# LMP848x_Breakout_v0_1.net
KiCad netlist of a schematic drawn in EAGLE
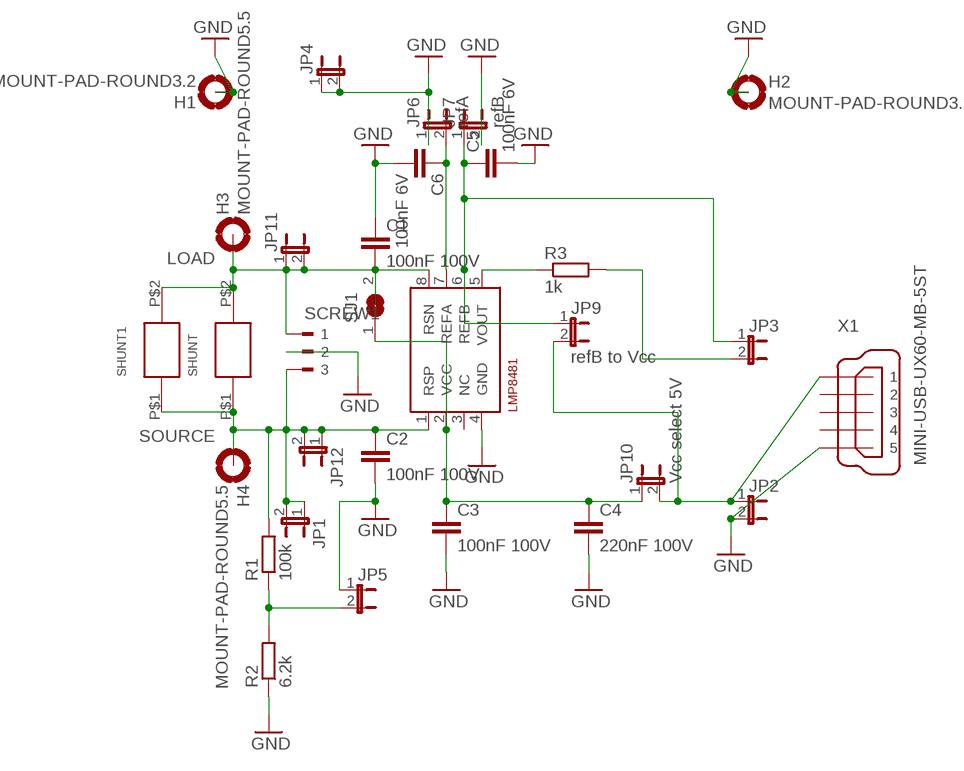
[diagram p0: schematic, sheet 1]

(export (version "E")
  (design (tool "Eeschema 10.0.6"))
  (components
    (comp (ref "C1")
      (value "100nF 100V")
      (footprint "eagle-import:C0805")
      (libsource (lib "eagle-import") (part "C-EUC0805"))
    )
    (comp (ref "C2")
      (value "100nF 100V")
      (footprint "eagle-import:C0805")
      (libsource (lib "eagle-import") (part "C-EUC0805"))
    )
    (comp (ref "C3")
      (value "100nF 100V")
      (footprint "eagle-import:C0805")
      (libsource (lib "eagle-import") (part "C-EUC0805"))
    )
    (comp (ref "C4")
      (value "220nF 100V")
      (footprint "eagle-import:C0805")
      (libsource (lib "eagle-import") (part "C-EUC0805"))
    )
    (comp (ref "C5")
      (value "100nF 6V")
      (footprint "eagle-import:C0805")
      (libsource (lib "eagle-import") (part "C-EUC0805"))
    )
    (comp (ref "C6")
      (value "100nF 6V")
      (footprint "eagle-import:C0805")
      (libsource (lib "eagle-import") (part "C-EUC0805"))
    )
    (comp (ref "H1")
      (value "MOUNT-PAD-ROUND3.2")
      (footprint "eagle-import:3,2-PAD")
      (libsource (lib "eagle-import") (part "MOUNT-PAD-ROUND3.2"))
    )
    (comp (ref "H2")
      (value "MOUNT-PAD-ROUND3.2")
      (footprint "eagle-import:3,2-PAD")
      (libsource (lib "eagle-import") (part "MOUNT-PAD-ROUND3.2"))
    )
    (comp (ref "H3")
      (value "MOUNT-PAD-ROUND5.5")
      (footprint "eagle-import:5,5-PAD")
      (libsource (lib "eagle-import") (part "MOUNT-PAD-ROUND5.5"))
    )
    (comp (ref "H4")
      (value "MOUNT-PAD-ROUND5.5")
      (footprint "eagle-import:5,5-PAD")
      (libsource (lib "eagle-import") (part "MOUNT-PAD-ROUND5.5"))
    )
    (comp (ref "JP1")
      (value "JP1E")
      (footprint "eagle-import:JP1")
      (libsource (lib "eagle-import") (part "JP1E"))
    )
    (comp (ref "JP2")
      (value "JP1E")
      (footprint "eagle-import:JP1")
      (libsource (lib "eagle-import") (part "JP1E"))
    )
    (comp (ref "JP3")
      (value "JP1E")
      (footprint "eagle-import:JP1")
      (libsource (lib "eagle-import") (part "JP1E"))
    )
    (comp (ref "JP4")
      (value "JP1E")
      (footprint "eagle-import:JP1")
      (libsource (lib "eagle-import") (part "JP1E"))
    )
    (comp (ref "JP5")
      (value "JP1E")
      (footprint "eagle-import:JP1")
      (libsource (lib "eagle-import") (part "JP1E"))
    )
    (comp (ref "JP6")
      (value "refA")
      (footprint "eagle-import:JP1")
      (libsource (lib "eagle-import") (part "JP1E"))
    )
    (comp (ref "JP7")
      (value "refB")
      (footprint "eagle-import:JP1")
      (libsource (lib "eagle-import") (part "JP1E"))
    )
    (comp (ref "JP9")
      (value "refB to Vcc")
      (footprint "eagle-import:JP1")
      (libsource (lib "eagle-import") (part "JP1E"))
    )
    (comp (ref "JP10")
      (value "Vcc select 5V")
      (footprint "eagle-import:JP1")
      (libsource (lib "eagle-import") (part "JP1E"))
    )
    (comp (ref "JP11")
      (value "JP1E")
      (footprint "eagle-import:JP1")
      (libsource (lib "eagle-import") (part "JP1E"))
    )
    (comp (ref "JP12")
      (value "JP1E")
      (footprint "eagle-import:JP1")
      (libsource (lib "eagle-import") (part "JP1E"))
    )
    (comp (ref "LMP8481")
      (value "LMP8481-H")
      (footprint "eagle-import:S-PDSO-G08")
      (libsource (lib "eagle-import") (part "LMP8481-H"))
    )
    (comp (ref "R1")
      (value "100k")
      (footprint "eagle-import:0207_7")
      (libsource (lib "eagle-import") (part "R-EU_0207/7"))
    )
    (comp (ref "R2")
      (value "6.2k")
      (footprint "eagle-import:0207_7")
      (libsource (lib "eagle-import") (part "R-EU_0207/7"))
    )
    (comp (ref "R3")
      (value "1k")
      (footprint "eagle-import:0204_5")
      (libsource (lib "eagle-import") (part "R-EU_0204/5"))
    )
    (comp (ref "SCREW1")
      (value "180-3")
      (footprint "eagle-import:180-3")
      (libsource (lib "eagle-import") (part "180-3"))
    )
    (comp (ref "SHUNT")
      (value "EBW_SERIES_15.2MM")
      (footprint "eagle-import:EBW_SERIES_15.2MM")
      (libsource (lib "eagle-import") (part "EBW_SERIES_15.2MM"))
    )
    (comp (ref "SHUNT1")
      (value "EBW_SERIES_15.2MM")
      (footprint "eagle-import:EBW_SERIES_15.2MM")
      (libsource (lib "eagle-import") (part "EBW_SERIES_15.2MM"))
    )
    (comp (ref "SJ1") (value "SJ") (footprint "eagle-import:SJ") (libsource (lib "eagle-import") (part "SJ")))
    (comp (ref "X1")
      (value "MINI-USB-UX60-MB-5ST")
      (footprint "eagle-import:UX60-MB-5ST")
      (libsource (lib "eagle-import") (part "MINI-USB-UX60-MB-5ST"))
    )
  )
  (nets
    (net (code "1") (name "/LOAD") (class "Default")
      (node (ref "C1") (pin "2") (pinfunction "2_2") (pintype "passive"))
      (node (ref "H3") (pin "B5,5") (pinfunction "MOUNT_B5,5") (pintype "passive"))
      (node (ref "JP11") (pin "1") (pinfunction "1_1") (pintype "passive"))
      (node (ref "JP11") (pin "2") (pinfunction "2_2") (pintype "passive"))
      (node (ref "LMP8481") (pin "8") (pinfunction "RSN_8") (pintype "bidirectional"))
      (node (ref "SCREW1") (pin "1") (pinfunction "1_1") (pintype "passive"))
      (node (ref "SHUNT") (pin "P$2") (pinfunction "P$2_P$2") (pintype "bidirectional"))
      (node (ref "SHUNT1") (pin "P$2") (pinfunction "P$2_P$2") (pintype "bidirectional"))
      (node (ref "SJ1") (pin "2") (pinfunction "2_2") (pintype "passive"))
    )
    (net (code "2") (name "/SOURCE") (class "Default")
      (node (ref "C2") (pin "1") (pinfunction "1_1") (pintype "passive"))
      (node (ref "H4") (pin "B5,5") (pinfunction "MOUNT_B5,5") (pintype "passive"))
      (node (ref "JP1") (pin "1") (pinfunction "1_1") (pintype "passive"))
      (node (ref "JP1") (pin "2") (pinfunction "2_2") (pintype "passive"))
      (node (ref "JP12") (pin "1") (pinfunction "1_1") (pintype "passive"))
      (node (ref "JP12") (pin "2") (pinfunction "2_2") (pintype "passive"))
      (node (ref "LMP8481") (pin "1") (pinfunction "RSP_1") (pintype "bidirectional"))
      (node (ref "R1") (pin "2") (pinfunction "2_2") (pintype "passive"))
      (node (ref "SCREW1") (pin "3") (pinfunction "3_3") (pintype "passive"))
      (node (ref "SHUNT") (pin "P$1") (pinfunction "P$1_P$1") (pintype "bidirectional"))
      (node (ref "SHUNT1") (pin "P$1") (pinfunction "P$1_P$1") (pintype "bidirectional"))
    )
    (net (code "3") (name "GND") (class "Default")
      (node (ref "C1") (pin "1") (pinfunction "1_1") (pintype "passive"))
      (node (ref "C2") (pin "2") (pinfunction "2_2") (pintype "passive"))
      (node (ref "C3") (pin "2") (pinfunction "2_2") (pintype "passive"))
      (node (ref "C4") (pin "2") (pinfunction "2_2") (pintype "passive"))
      (node (ref "C5") (pin "2") (pinfunction "2_2") (pintype "passive"))
      (node (ref "C6") (pin "2") (pinfunction "2_2") (pintype "passive"))
      (node (ref "H1") (pin "B3,2") (pinfunction "MOUNT_B3,2") (pintype "passive"))
      (node (ref "H2") (pin "B3,2") (pinfunction "MOUNT_B3,2") (pintype "passive"))
      (node (ref "JP2") (pin "2") (pinfunction "2_2") (pintype "passive"))
      (node (ref "JP4") (pin "1") (pinfunction "1_1") (pintype "passive"))
      (node (ref "JP4") (pin "2") (pinfunction "2_2") (pintype "passive"))
      (node (ref "JP5") (pin "1") (pinfunction "1_1") (pintype "passive"))
      (node (ref "JP6") (pin "1") (pinfunction "1_1") (pintype "passive"))
      (node (ref "JP7") (pin "2") (pinfunction "2_2") (pintype "passive"))
      (node (ref "LMP8481") (pin "4") (pinfunction "GND_4") (pintype "bidirectional"))
      (node (ref "R2") (pin "1") (pinfunction "1_1") (pintype "passive"))
      (node (ref "SCREW1") (pin "2") (pinfunction "2_2") (pintype "passive"))
      (node (ref "X1") (pin "5") (pinfunction "5_5") (pintype "input"))
    )
    (net (code "4") (name "Net-(JP3-Pad2)") (class "Default")
      (node (ref "JP3") (pin "2") (pinfunction "2_2") (pintype "passive"))
      (node (ref "R3") (pin "2") (pinfunction "2_2") (pintype "passive"))
    )
    (net (code "5") (name "Net-(JP5-Pad2)") (class "Default")
      (node (ref "JP5") (pin "2") (pinfunction "2_2") (pintype "passive"))
      (node (ref "R1") (pin "1") (pinfunction "1_1") (pintype "passive"))
      (node (ref "R2") (pin "2") (pinfunction "2_2") (pintype "passive"))
    )
    (net (code "6") (name "Net-(JP10-Pad2)") (class "Default")
      (node (ref "JP10") (pin "2") (pinfunction "2_2") (pintype "passive"))
      (node (ref "JP2") (pin "1") (pinfunction "1_1") (pintype "passive"))
      (node (ref "JP9") (pin "2") (pinfunction "2_2") (pintype "passive"))
      (node (ref "X1") (pin "1") (pinfunction "1_1") (pintype "input"))
    )
    (net (code "7") (name "Net-(LMP8481-REFA)") (class "Default")
      (node (ref "C6") (pin "1") (pinfunction "1_1") (pintype "passive"))
      (node (ref "JP6") (pin "2") (pinfunction "2_2") (pintype "passive"))
      (node (ref "LMP8481") (pin "7") (pinfunction "REFA_7") (pintype "bidirectional"))
    )
    (net (code "8") (name "Net-(LMP8481-REFB)") (class "Default")
      (node (ref "C5") (pin "1") (pinfunction "1_1") (pintype "passive"))
      (node (ref "JP3") (pin "1") (pinfunction "1_1") (pintype "passive"))
      (node (ref "JP7") (pin "1") (pinfunction "1_1") (pintype "passive"))
      (node (ref "JP9") (pin "1") (pinfunction "1_1") (pintype "passive"))
      (node (ref "LMP8481") (pin "6") (pinfunction "REFB_6") (pintype "bidirectional"))
    )
    (net (code "9") (name "Net-(LMP8481-VCC)") (class "Default")
      (node (ref "C3") (pin "1") (pinfunction "1_1") (pintype "passive"))
      (node (ref "C4") (pin "1") (pinfunction "1_1") (pintype "passive"))
      (node (ref "JP10") (pin "1") (pinfunction "1_1") (pintype "passive"))
      (node (ref "LMP8481") (pin "2") (pinfunction "VCC_2") (pintype "bidirectional"))
      (node (ref "SJ1") (pin "1") (pinfunction "1_1") (pintype "passive"))
    )
    (net (code "10") (name "Net-(LMP8481-VOUT)") (class "Default")
      (node (ref "LMP8481") (pin "5") (pinfunction "VOUT_5") (pintype "bidirectional"))
      (node (ref "R3") (pin "1") (pinfunction "1_1") (pintype "passive"))
    )
    (net (code "11") (name "unconnected-(LMP8481-NC-Pad3)") (class "Default")
      (node (ref "LMP8481") (pin "3") (pinfunction "NC_3") (pintype "bidirectional"))
    )
    (net (code "12") (name "unconnected-(X1-Pad2)") (class "Default")
      (node (ref "X1") (pin "2") (pinfunction "2_2") (pintype "input"))
    )
    (net (code "13") (name "unconnected-(X1-Pad3)") (class "Default")
      (node (ref "X1") (pin "3") (pinfunction "3_3") (pintype "input"))
    )
    (net (code "14") (name "unconnected-(X1-Pad4)") (class "Default")
      (node (ref "X1") (pin "4") (pinfunction "4_4") (pintype "input"))
    )
  )
)
